# Power_Supply_CurrentMeasurement.net
KiCad netlist of a schematic drawn in Altium Designer
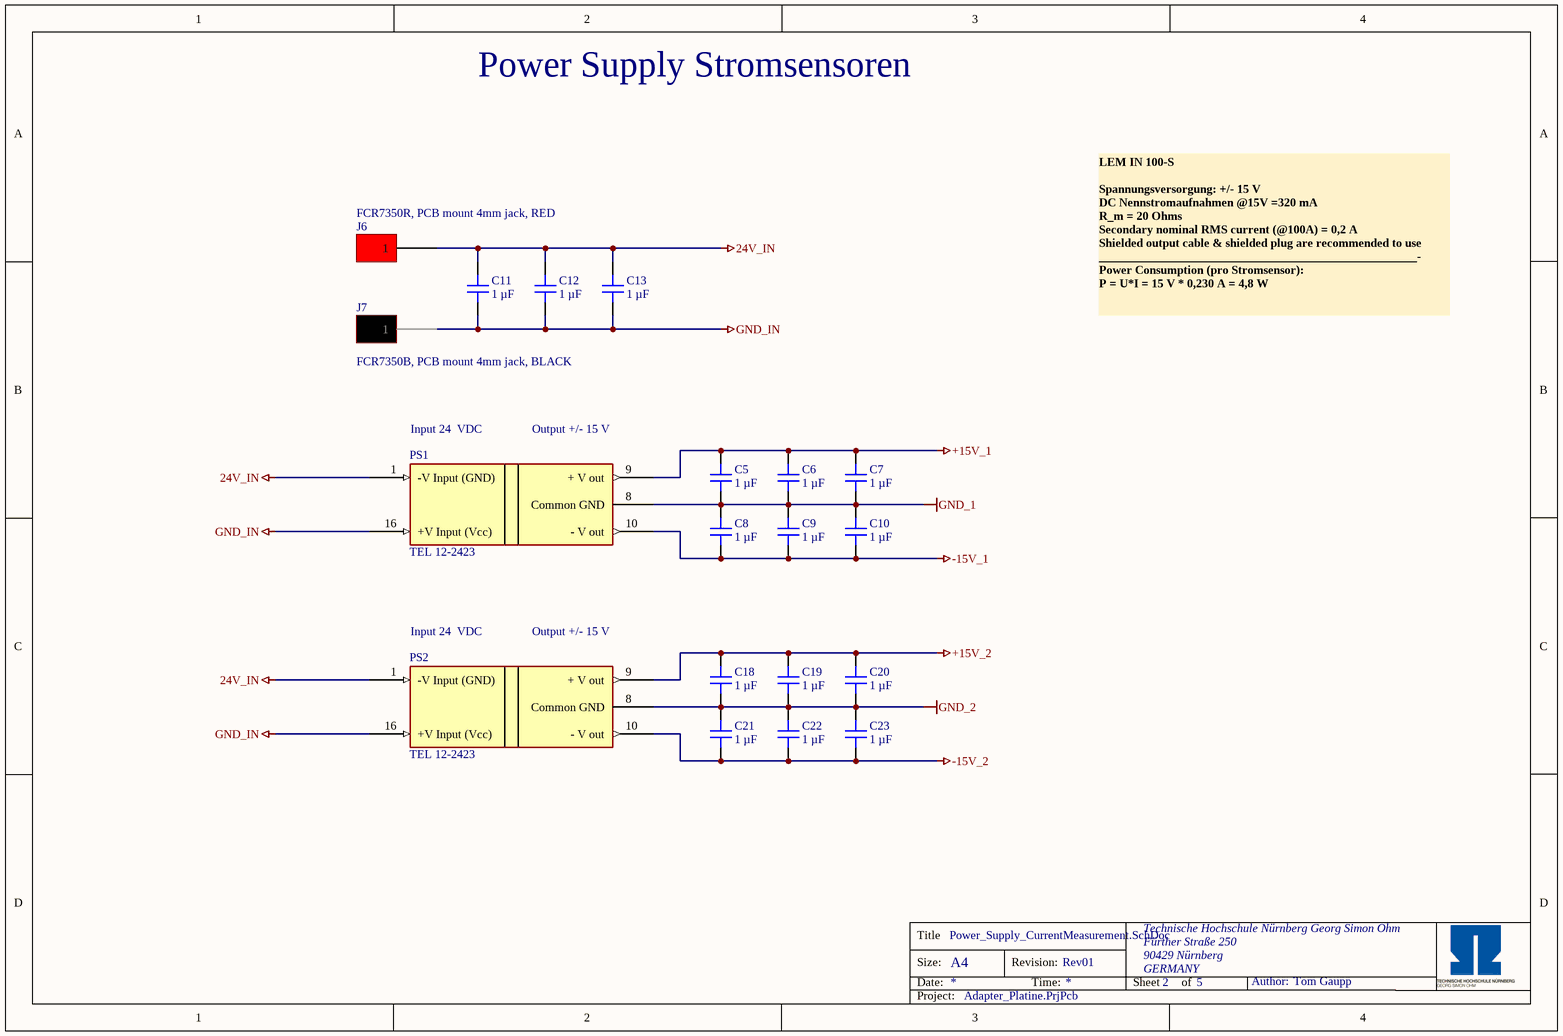
[diagram p0: Power_Supply_CurrentMeasurement.SchDoc]

(export (version "E")
  (design (tool "Eeschema 10.0.6"))
  (components
    (comp (ref "C5")
      (value "1 µF")
      (footprint "C_0603")
      (description "50V 1uF X5R ±10% 0603  Multilayer Ceramic Capacitors MLCC - SMD/SMT ROHS")
      (fields
        (field (name "MANUFACTURER") "Samsung Electro-Mechanics")
        (field (name "MANUFACTURER PART NUMBER") "CL10A105KB8NNNC")
        (field (name "CREATED FROM") "MGremer")
      )
      (libsource (lib "user") (part "Capacitor"))
    )
    (comp (ref "C6")
      (value "1 µF")
      (footprint "C_0603")
      (description "50V 1uF X5R ±10% 0603  Multilayer Ceramic Capacitors MLCC - SMD/SMT ROHS")
      (fields
        (field (name "MANUFACTURER") "Samsung Electro-Mechanics")
        (field (name "MANUFACTURER PART NUMBER") "CL10A105KB8NNNC")
        (field (name "CREATED FROM") "MGremer")
      )
      (libsource (lib "user") (part "Capacitor"))
    )
    (comp (ref "C7")
      (value "1 µF")
      (footprint "C_0603")
      (description "50V 1uF X5R ±10% 0603  Multilayer Ceramic Capacitors MLCC - SMD/SMT ROHS")
      (fields
        (field (name "MANUFACTURER") "Samsung Electro-Mechanics")
        (field (name "MANUFACTURER PART NUMBER") "CL10A105KB8NNNC")
        (field (name "CREATED FROM") "MGremer")
      )
      (libsource (lib "user") (part "Capacitor"))
    )
    (comp (ref "C8")
      (value "1 µF")
      (footprint "C_0603")
      (description "50V 1uF X5R ±10% 0603  Multilayer Ceramic Capacitors MLCC - SMD/SMT ROHS")
      (fields
        (field (name "MANUFACTURER") "Samsung Electro-Mechanics")
        (field (name "MANUFACTURER PART NUMBER") "CL10A105KB8NNNC")
        (field (name "CREATED FROM") "MGremer")
      )
      (libsource (lib "user") (part "Capacitor"))
    )
    (comp (ref "C9")
      (value "1 µF")
      (footprint "C_0603")
      (description "50V 1uF X5R ±10% 0603  Multilayer Ceramic Capacitors MLCC - SMD/SMT ROHS")
      (fields
        (field (name "MANUFACTURER") "Samsung Electro-Mechanics")
        (field (name "MANUFACTURER PART NUMBER") "CL10A105KB8NNNC")
        (field (name "CREATED FROM") "MGremer")
      )
      (libsource (lib "user") (part "Capacitor"))
    )
    (comp (ref "C10")
      (value "1 µF")
      (footprint "C_0603")
      (description "50V 1uF X5R ±10% 0603  Multilayer Ceramic Capacitors MLCC - SMD/SMT ROHS")
      (fields
        (field (name "MANUFACTURER") "Samsung Electro-Mechanics")
        (field (name "MANUFACTURER PART NUMBER") "CL10A105KB8NNNC")
        (field (name "CREATED FROM") "MGremer")
      )
      (libsource (lib "user") (part "Capacitor"))
    )
    (comp (ref "C11")
      (value "1 µF")
      (footprint "C_0603")
      (description "50V 1uF X5R ±10% 0603  Multilayer Ceramic Capacitors MLCC - SMD/SMT ROHS")
      (fields
        (field (name "MANUFACTURER") "Samsung Electro-Mechanics")
        (field (name "MANUFACTURER PART NUMBER") "CL10A105KB8NNNC")
        (field (name "CREATED FROM") "MGremer")
      )
      (libsource (lib "user") (part "Capacitor"))
    )
    (comp (ref "C12")
      (value "1 µF")
      (footprint "C_0603")
      (description "50V 1uF X5R ±10% 0603  Multilayer Ceramic Capacitors MLCC - SMD/SMT ROHS")
      (fields
        (field (name "MANUFACTURER") "Samsung Electro-Mechanics")
        (field (name "MANUFACTURER PART NUMBER") "CL10A105KB8NNNC")
        (field (name "CREATED FROM") "MGremer")
      )
      (libsource (lib "user") (part "Capacitor"))
    )
    (comp (ref "C13")
      (value "1 µF")
      (footprint "C_0603")
      (description "50V 1uF X5R ±10% 0603  Multilayer Ceramic Capacitors MLCC - SMD/SMT ROHS")
      (fields
        (field (name "MANUFACTURER") "Samsung Electro-Mechanics")
        (field (name "MANUFACTURER PART NUMBER") "CL10A105KB8NNNC")
        (field (name "CREATED FROM") "MGremer")
      )
      (libsource (lib "user") (part "Capacitor"))
    )
    (comp (ref "C18")
      (value "1 µF")
      (footprint "C_0603")
      (description "50V 1uF X5R ±10% 0603  Multilayer Ceramic Capacitors MLCC - SMD/SMT ROHS")
      (fields
        (field (name "MANUFACTURER") "Samsung Electro-Mechanics")
        (field (name "MANUFACTURER PART NUMBER") "CL10A105KB8NNNC")
        (field (name "CREATED FROM") "MGremer")
      )
      (libsource (lib "user") (part "Capacitor"))
    )
    (comp (ref "C19")
      (value "1 µF")
      (footprint "C_0603")
      (description "50V 1uF X5R ±10% 0603  Multilayer Ceramic Capacitors MLCC - SMD/SMT ROHS")
      (fields
        (field (name "MANUFACTURER") "Samsung Electro-Mechanics")
        (field (name "MANUFACTURER PART NUMBER") "CL10A105KB8NNNC")
        (field (name "CREATED FROM") "MGremer")
      )
      (libsource (lib "user") (part "Capacitor"))
    )
    (comp (ref "C20")
      (value "1 µF")
      (footprint "C_0603")
      (description "50V 1uF X5R ±10% 0603  Multilayer Ceramic Capacitors MLCC - SMD/SMT ROHS")
      (fields
        (field (name "MANUFACTURER") "Samsung Electro-Mechanics")
        (field (name "MANUFACTURER PART NUMBER") "CL10A105KB8NNNC")
        (field (name "CREATED FROM") "MGremer")
      )
      (libsource (lib "user") (part "Capacitor"))
    )
    (comp (ref "C21")
      (value "1 µF")
      (footprint "C_0603")
      (description "50V 1uF X5R ±10% 0603  Multilayer Ceramic Capacitors MLCC - SMD/SMT ROHS")
      (fields
        (field (name "MANUFACTURER") "Samsung Electro-Mechanics")
        (field (name "MANUFACTURER PART NUMBER") "CL10A105KB8NNNC")
        (field (name "CREATED FROM") "MGremer")
      )
      (libsource (lib "user") (part "Capacitor"))
    )
    (comp (ref "C22")
      (value "1 µF")
      (footprint "C_0603")
      (description "50V 1uF X5R ±10% 0603  Multilayer Ceramic Capacitors MLCC - SMD/SMT ROHS")
      (fields
        (field (name "MANUFACTURER") "Samsung Electro-Mechanics")
        (field (name "MANUFACTURER PART NUMBER") "CL10A105KB8NNNC")
        (field (name "CREATED FROM") "MGremer")
      )
      (libsource (lib "user") (part "Capacitor"))
    )
    (comp (ref "C23")
      (value "1 µF")
      (footprint "C_0603")
      (description "50V 1uF X5R ±10% 0603  Multilayer Ceramic Capacitors MLCC - SMD/SMT ROHS")
      (fields
        (field (name "MANUFACTURER") "Samsung Electro-Mechanics")
        (field (name "MANUFACTURER PART NUMBER") "CL10A105KB8NNNC")
        (field (name "CREATED FROM") "MGremer")
      )
      (libsource (lib "user") (part "Capacitor"))
    )
    (comp (ref "J6")
      (value "FCR7350R, PCB mount 4mm jack, RED")
      (footprint "FCR7350")
      (description "FCR7350B, 1000V, 24A, RED")
      (fields
        (field (name "MANUFACTURER PART NUMBER") "FCR7350R")
        (field (name "MANUFACTURER") "Cliff")
        (field (name "CREATED FROM") "DHufnagel")
      )
      (libsource (lib "user") (part "FCR7350R"))
    )
    (comp (ref "J7")
      (value "FCR7350B, PCB mount 4mm jack, BLACK")
      (footprint "FCR7350")
      (description "FCR7350B, 1000V, 24A, BLACK")
      (fields
        (field (name "MANUFACTURER PART NUMBER") "FCR7350B")
        (field (name "MANUFACTURER") "Cliff")
        (field (name "CREATED FROM") "DHufnagel")
      )
      (libsource (lib "user") (part "FCR7350B"))
    )
    (comp (ref "PS1")
      (value "TEL 12-2423")
      (footprint "eigene_lib_alt:TEL 12-2423")
      (description "Isolierte DC/DC-Wandler – Durchsteckmontage 18-36Vin+/-15V 400mA 12W DIP Iso")
      (libsource (lib "eigene_lib_alt") (part "TEL 12-2423"))
    )
    (comp (ref "PS2")
      (value "TEL 12-2423")
      (footprint "eigene_lib_alt:TEL 12-2423")
      (description "Isolierte DC/DC-Wandler – Durchsteckmontage 18-36Vin+/-15V 400mA 12W DIP Iso")
      (libsource (lib "eigene_lib_alt") (part "TEL 12-2423"))
    )
  )
  (nets
    (net (code "1") (name "+15V_1") (class "Default")
      (node (ref "C5") (pin "2") (pinfunction "2_2") (pintype "passive"))
      (node (ref "C6") (pin "2") (pinfunction "2_2") (pintype "passive"))
      (node (ref "C7") (pin "2") (pinfunction "2_2") (pintype "passive"))
      (node (ref "PS1") (pin "9") (pinfunction "+_V_out_9") (pintype "output"))
    )
    (net (code "2") (name "+15V_2") (class "Default")
      (node (ref "C18") (pin "2") (pinfunction "2_2") (pintype "passive"))
      (node (ref "C19") (pin "2") (pinfunction "2_2") (pintype "passive"))
      (node (ref "C20") (pin "2") (pinfunction "2_2") (pintype "passive"))
      (node (ref "PS2") (pin "9") (pinfunction "+_V_out_9") (pintype "output"))
    )
    (net (code "3") (name "-15V_1") (class "Default")
      (node (ref "C10") (pin "1") (pinfunction "1_1") (pintype "passive"))
      (node (ref "C8") (pin "1") (pinfunction "1_1") (pintype "passive"))
      (node (ref "C9") (pin "1") (pinfunction "1_1") (pintype "passive"))
      (node (ref "PS1") (pin "10") (pinfunction "-_V_out_10") (pintype "output"))
    )
    (net (code "4") (name "-15V_2") (class "Default")
      (node (ref "C21") (pin "1") (pinfunction "1_1") (pintype "passive"))
      (node (ref "C22") (pin "1") (pinfunction "1_1") (pintype "passive"))
      (node (ref "C23") (pin "1") (pinfunction "1_1") (pintype "passive"))
      (node (ref "PS2") (pin "10") (pinfunction "-_V_out_10") (pintype "output"))
    )
    (net (code "5") (name "24V_IN") (class "Default")
      (node (ref "C11") (pin "1") (pinfunction "1_1") (pintype "passive"))
      (node (ref "C12") (pin "1") (pinfunction "1_1") (pintype "passive"))
      (node (ref "C13") (pin "1") (pinfunction "1_1") (pintype "passive"))
      (node (ref "J6") (pin "1") (pinfunction "1_1") (pintype "passive"))
      (node (ref "PS1") (pin "1") (pinfunction "-V_Input_(GND)_1") (pintype "input"))
      (node (ref "PS2") (pin "1") (pinfunction "-V_Input_(GND)_1") (pintype "input"))
    )
    (net (code "6") (name "GND_1") (class "Default")
      (node (ref "C10") (pin "2") (pinfunction "2_2") (pintype "passive"))
      (node (ref "C5") (pin "1") (pinfunction "1_1") (pintype "passive"))
      (node (ref "C6") (pin "1") (pinfunction "1_1") (pintype "passive"))
      (node (ref "C7") (pin "1") (pinfunction "1_1") (pintype "passive"))
      (node (ref "C8") (pin "2") (pinfunction "2_2") (pintype "passive"))
      (node (ref "C9") (pin "2") (pinfunction "2_2") (pintype "passive"))
      (node (ref "PS1") (pin "8") (pinfunction "Common_GND_8") (pintype "passive"))
    )
    (net (code "7") (name "GND_2") (class "Default")
      (node (ref "C18") (pin "1") (pinfunction "1_1") (pintype "passive"))
      (node (ref "C19") (pin "1") (pinfunction "1_1") (pintype "passive"))
      (node (ref "C20") (pin "1") (pinfunction "1_1") (pintype "passive"))
      (node (ref "C21") (pin "2") (pinfunction "2_2") (pintype "passive"))
      (node (ref "C22") (pin "2") (pinfunction "2_2") (pintype "passive"))
      (node (ref "C23") (pin "2") (pinfunction "2_2") (pintype "passive"))
      (node (ref "PS2") (pin "8") (pinfunction "Common_GND_8") (pintype "passive"))
    )
    (net (code "8") (name "GND_IN") (class "Default")
      (node (ref "C11") (pin "2") (pinfunction "2_2") (pintype "passive"))
      (node (ref "C12") (pin "2") (pinfunction "2_2") (pintype "passive"))
      (node (ref "C13") (pin "2") (pinfunction "2_2") (pintype "passive"))
      (node (ref "J7") (pin "1") (pinfunction "1_1") (pintype "passive"))
      (node (ref "PS1") (pin "16") (pinfunction "+V_Input_(Vcc)_16") (pintype "input"))
      (node (ref "PS2") (pin "16") (pinfunction "+V_Input_(Vcc)_16") (pintype "input"))
    )
  )
)
